# Power_Regulation.net
KiCad netlist of a schematic drawn in Altium Designer
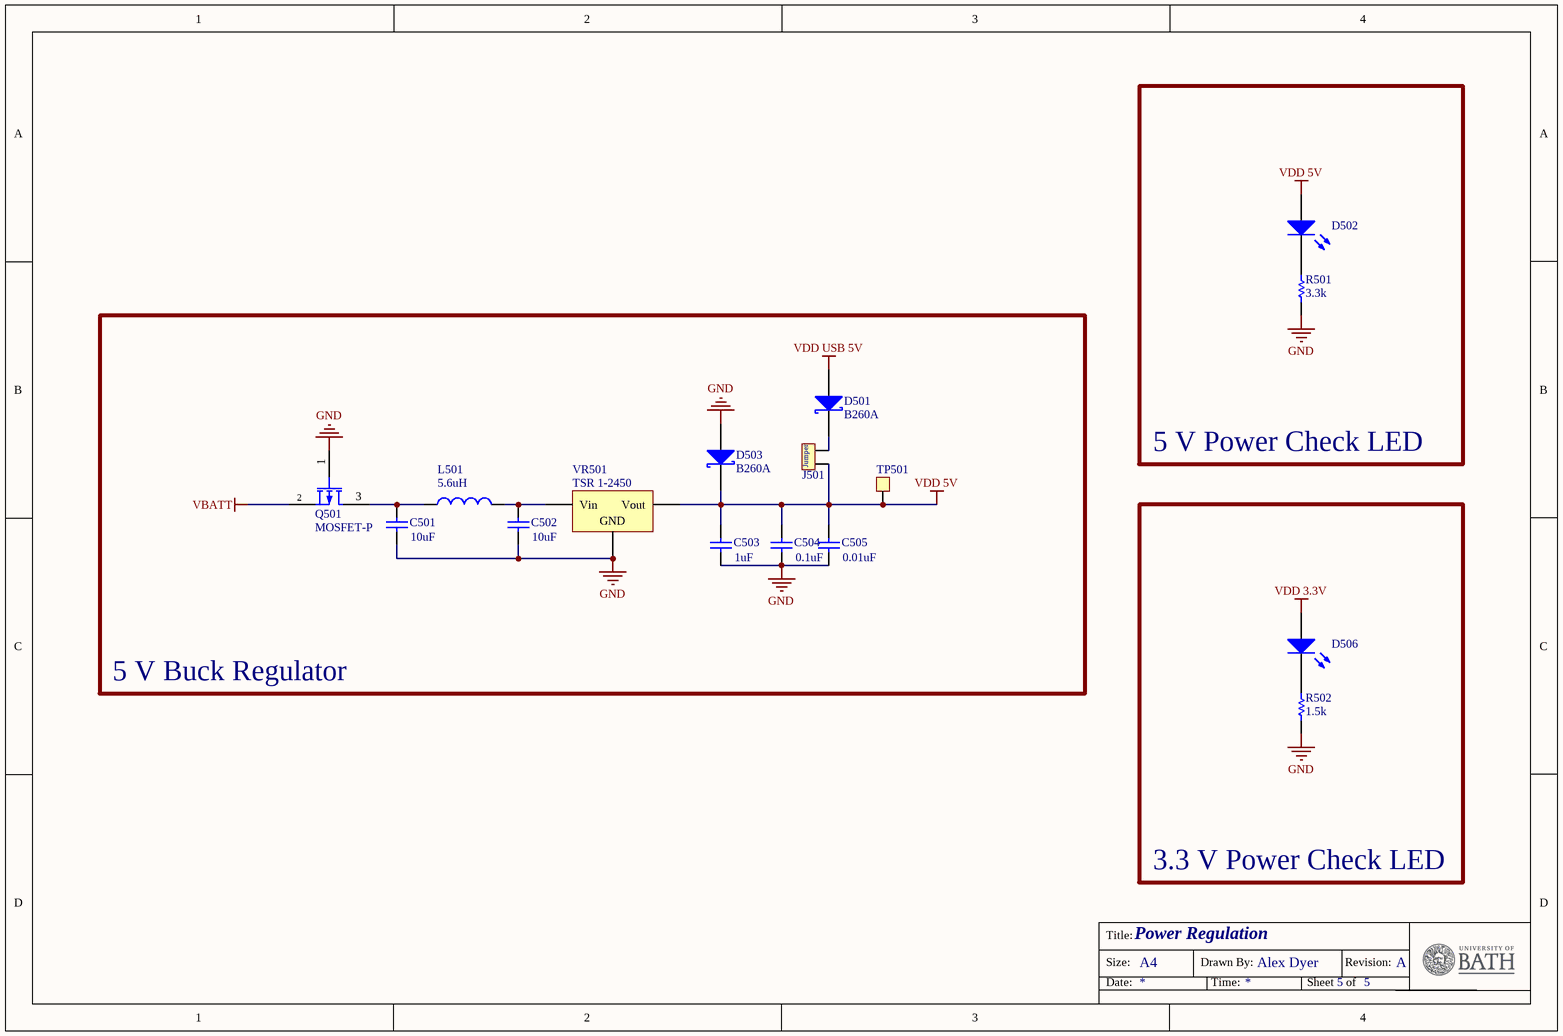
[diagram p0: Power Regulation.SchDoc]

(export (version "E")
  (design (tool "Eeschema 10.0.6"))
  (components
    (comp (ref "C501")
      (value "10uF")
      (footprint "0805 Cap")
      (fields (field (name "Comment") "C2012X5R1V106K085AC") (field (name "PUBLISHER") "Altium Limited"))
      (libsource (lib "Miscellaneous Devices") (part "Cap"))
    )
    (comp (ref "C502")
      (value "10uF")
      (footprint "0805 Cap")
      (fields (field (name "Comment") "C2012X5R1V106K085AC") (field (name "PUBLISHER") "Altium Limited"))
      (libsource (lib "Miscellaneous Devices") (part "Cap"))
    )
    (comp (ref "C503")
      (value "1uF")
      (footprint "0805 Cap")
      (fields (field (name "Comment") "C2012X5R1V106K085AC") (field (name "PUBLISHER") "Altium Limited"))
      (libsource (lib "Miscellaneous Devices") (part "Cap"))
    )
    (comp (ref "C504")
      (value "0.1uF")
      (footprint "0805 Cap")
      (fields (field (name "Comment") "C2012X5R1V106K085AC") (field (name "PUBLISHER") "Altium Limited"))
      (libsource (lib "Miscellaneous Devices") (part "Cap"))
    )
    (comp (ref "C505")
      (value "0.01uF")
      (footprint "0805 Cap")
      (fields (field (name "Comment") "C2012X5R1V106K085AC") (field (name "PUBLISHER") "Altium Limited"))
      (libsource (lib "Miscellaneous Devices") (part "Cap"))
    )
    (comp (ref "D501")
      (value "B260A")
      (footprint "SMA (DO-214AC)")
      (description "Schottky Diode")
      (libsource (lib "Miscellaneous Devices") (part "D Schottky"))
    )
    (comp (ref "D502")
      (value "LED2")
      (footprint "SML-211 Series")
      (description "Typical RED, GREEN, YELLOW, AMBER GaAs LED")
      (libsource (lib "Miscellaneous Devices") (part "LED2"))
    )
    (comp (ref "D503")
      (value "B260A")
      (footprint "SMA (DO-214AC)")
      (description "Schottky Diode")
      (libsource (lib "Miscellaneous Devices") (part "D Schottky"))
    )
    (comp (ref "D506")
      (value "LED2")
      (footprint "SML-211 Series")
      (description "Typical RED, GREEN, YELLOW, AMBER GaAs LED")
      (libsource (lib "Miscellaneous Devices") (part "LED2"))
    )
    (comp (ref "J501")
      (value "Jumper")
      (footprint "2.54mm 2 pin Jumper")
      (libsource (lib "FYP_Drone") (part "Jumper"))
    )
    (comp (ref "L501")
      (value "5.6uH")
      (footprint "SRR1280A")
      (description "https://www.mouser.co.uk/ProductDetail/Bourns/SRR1240-5R6M?qs=xrpI9KL%2FXvsXaYuKX%252BElwQ%3D%3D")
      (fields (field (name "Comment") "SRR1280A-331K") (field (name "PUBLISHER") "Altium Limited"))
      (libsource (lib "Miscellaneous Devices") (part "Inductor"))
    )
    (comp (ref "Q501")
      (value "MOSFET-P")
      (footprint "SOT95P230X110-3N")
      (description "P-Channel MOSFET")
      (libsource (lib "Miscellaneous Devices") (part "MOSFET-P"))
    )
    (comp (ref "R501")
      (value "3.3k")
      (footprint "0603")
      (description "Resistor")
      (fields (field (name "Comment") "0603") (field (name "PUBLISHER") "Altium Limited"))
      (libsource (lib "Miscellaneous Devices") (part "Res1"))
    )
    (comp (ref "R502")
      (value "1.5k")
      (footprint "0603")
      (description "Resistor")
      (fields (field (name "Comment") "0603") (field (name "PUBLISHER") "Altium Limited"))
      (libsource (lib "Miscellaneous Devices") (part "Res1"))
    )
    (comp (ref "TP501")
      (value "Test Point")
      (footprint "Test Point THT 1mm")
      (libsource (lib "FYP_Drone") (part "Test Point"))
    )
    (comp (ref "VR501")
      (value "TSR 1-2450")
      (footprint "TRACOPOWER TSR")
      (description "https://uk.farnell.com/tracopower/tsr-1-2450/converter-dc-dc-5v-1a-sip/dp/1696320")
      (fields (field (name "PUBLISHER") "Altium Limited"))
      (libsource (lib "Miscellaneous Devices") (part "Volt Reg"))
    )
  )
  (nets
    (net (code "1") (name "GND") (class "Default")
      (node (ref "C501") (pin "1") (pinfunction "1_1") (pintype "passive"))
      (node (ref "C502") (pin "1") (pinfunction "1_1") (pintype "passive"))
      (node (ref "C503") (pin "1") (pinfunction "1_1") (pintype "passive"))
      (node (ref "C504") (pin "1") (pinfunction "1_1") (pintype "passive"))
      (node (ref "C505") (pin "1") (pinfunction "1_1") (pintype "passive"))
      (node (ref "D503") (pin "1") (pinfunction "A_1") (pintype "passive"))
      (node (ref "Q501") (pin "1") (pinfunction "G_1") (pintype "passive"))
      (node (ref "R501") (pin "1") (pinfunction "1_1") (pintype "passive"))
      (node (ref "R502") (pin "1") (pinfunction "1_1") (pintype "passive"))
      (node (ref "VR501") (pin "2") (pinfunction "GND_2") (pintype "passive"))
    )
    (net (code "2") (name "Net-(D501-K)") (class "Default")
      (node (ref "D501") (pin "2") (pinfunction "K_2") (pintype "passive"))
      (node (ref "J501") (pin "1") (pintype "passive"))
    )
    (net (code "3") (name "Net-(D502-K)") (class "Default")
      (node (ref "D502") (pin "2") (pinfunction "K_2") (pintype "passive"))
      (node (ref "R501") (pin "2") (pinfunction "2_2") (pintype "passive"))
    )
    (net (code "4") (name "Net-(D506-K)") (class "Default")
      (node (ref "D506") (pin "2") (pinfunction "K_2") (pintype "passive"))
      (node (ref "R502") (pin "2") (pinfunction "2_2") (pintype "passive"))
    )
    (net (code "5") (name "Net-(Q501-D)") (class "Default")
      (node (ref "C501") (pin "2") (pinfunction "2_2") (pintype "passive"))
      (node (ref "L501") (pin "1") (pinfunction "1_1") (pintype "passive"))
      (node (ref "Q501") (pin "3") (pinfunction "D_3") (pintype "passive"))
    )
    (net (code "6") (name "Net-(VR501-Vin)") (class "Default")
      (node (ref "C502") (pin "2") (pinfunction "2_2") (pintype "passive"))
      (node (ref "L501") (pin "2") (pinfunction "2_2") (pintype "passive"))
      (node (ref "VR501") (pin "1") (pinfunction "Vin_1") (pintype "passive"))
    )
    (net (code "7") (name "VBATT") (class "Default")
      (node (ref "Q501") (pin "2") (pinfunction "S_2") (pintype "passive"))
    )
    (net (code "8") (name "VDD 3.3V") (class "Default")
      (node (ref "D506") (pin "1") (pinfunction "A_1") (pintype "passive"))
    )
    (net (code "9") (name "VDD 5V") (class "Default")
      (node (ref "C503") (pin "2") (pinfunction "2_2") (pintype "passive"))
      (node (ref "C504") (pin "2") (pinfunction "2_2") (pintype "passive"))
      (node (ref "C505") (pin "2") (pinfunction "2_2") (pintype "passive"))
      (node (ref "D502") (pin "1") (pinfunction "A_1") (pintype "passive"))
      (node (ref "D503") (pin "2") (pinfunction "K_2") (pintype "passive"))
      (node (ref "J501") (pin "2") (pintype "passive"))
      (node (ref "TP501") (pin "1") (pintype "passive"))
      (node (ref "VR501") (pin "3") (pinfunction "Vout_3") (pintype "passive"))
    )
    (net (code "10") (name "VDD USB 5V") (class "Default")
      (node (ref "D501") (pin "1") (pinfunction "A_1") (pintype "passive"))
    )
  )
)
